# RK3566_VO_Interface.net
KiCad netlist of a schematic drawn in Altium Designer
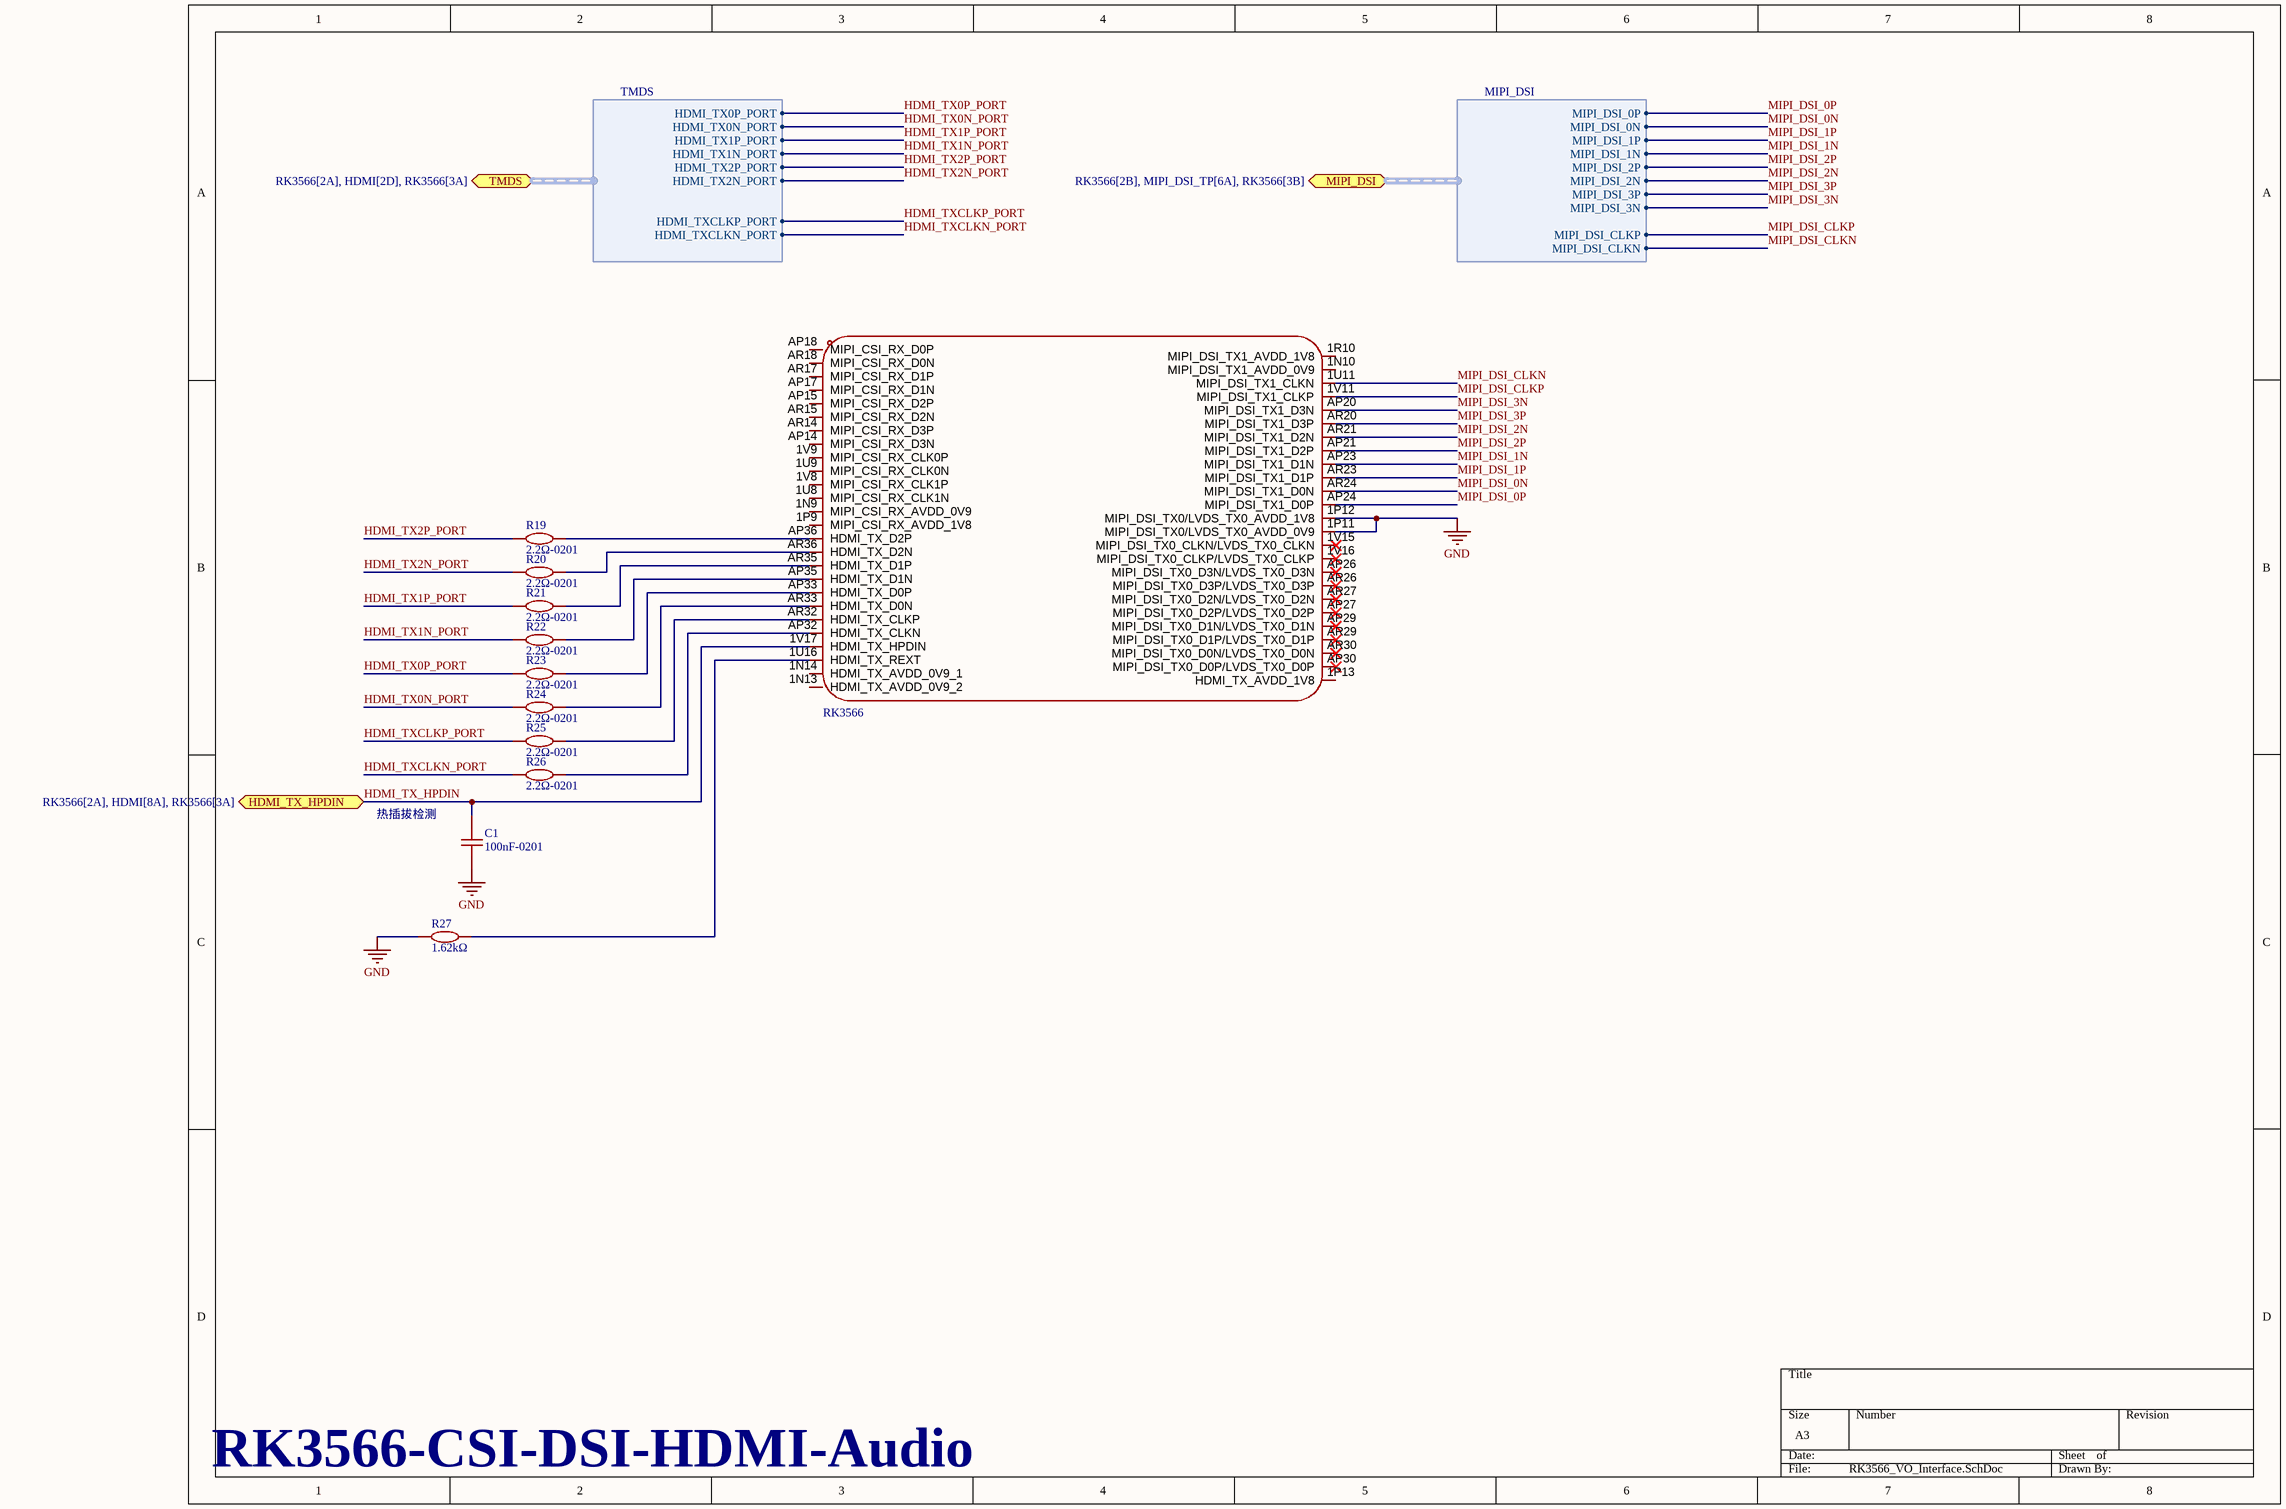
[diagram p0: RK3566_VO_Interface.SchDoc]

(export (version "E")
  (design (tool "Eeschema 10.0.6"))
  (components
    (comp (ref "C1")
      (value "100nF-0201")
      (footprint "C0402")
      (description "CL03A104KO3NNNC")
      (libsource (lib "RLC") (part "100nF-0201"))
    )
    (comp (ref "R19")
      (value "2.2Ω-0201")
      (footprint "R0201")
      (description "小尺寸、重量轻。降低组装成本,与贴片机匹配。适用于波峰焊和回流焊")
      (libsource (lib "RLC") (part "2.2Ω-0201"))
    )
    (comp (ref "R20")
      (value "2.2Ω-0201")
      (footprint "R0201")
      (description "小尺寸、重量轻。降低组装成本,与贴片机匹配。适用于波峰焊和回流焊")
      (libsource (lib "RLC") (part "2.2Ω-0201"))
    )
    (comp (ref "R21")
      (value "2.2Ω-0201")
      (footprint "R0201")
      (description "小尺寸、重量轻。降低组装成本,与贴片机匹配。适用于波峰焊和回流焊")
      (libsource (lib "RLC") (part "2.2Ω-0201"))
    )
    (comp (ref "R22")
      (value "2.2Ω-0201")
      (footprint "R0201")
      (description "小尺寸、重量轻。降低组装成本,与贴片机匹配。适用于波峰焊和回流焊")
      (libsource (lib "RLC") (part "2.2Ω-0201"))
    )
    (comp (ref "R23")
      (value "2.2Ω-0201")
      (footprint "R0201")
      (description "小尺寸、重量轻。降低组装成本,与贴片机匹配。适用于波峰焊和回流焊")
      (libsource (lib "RLC") (part "2.2Ω-0201"))
    )
    (comp (ref "R24")
      (value "2.2Ω-0201")
      (footprint "R0201")
      (description "小尺寸、重量轻。降低组装成本,与贴片机匹配。适用于波峰焊和回流焊")
      (libsource (lib "RLC") (part "2.2Ω-0201"))
    )
    (comp (ref "R25")
      (value "2.2Ω-0201")
      (footprint "R0201")
      (description "小尺寸、重量轻。降低组装成本,与贴片机匹配。适用于波峰焊和回流焊")
      (libsource (lib "RLC") (part "2.2Ω-0201"))
    )
    (comp (ref "R26")
      (value "2.2Ω-0201")
      (footprint "R0201")
      (description "小尺寸、重量轻。降低组装成本,与贴片机匹配。适用于波峰焊和回流焊")
      (libsource (lib "RLC") (part "2.2Ω-0201"))
    )
    (comp (ref "R27")
      (value "1.62kΩ")
      (footprint "R0402")
      (description "特性：无卤环氧树脂。符合RoHS标准。无铅端接产品符合RoHS要求。RoHS豁免电极、电阻元件和玻璃中含有的铅玻璃。减少对环境有害的废物。高组件和设备可靠性。应用：所有通用应用")
      (libsource (lib "RLC") (part "1.62kΩ"))
    )
    (comp (ref "U1")
      (value "RK3566")
      (footprint "BGA-565_L15.5-W14.4-P0.40_RK3566_1")
      (description "BGA-565(15.5x14.4)")
      (libsource (lib "IC") (part "RK3566"))
    )
  )
  (nets
    (net (code "3") (name "/HDMI_TX0N_PORT") (class "Default")
      (node (ref "R24") (pin "1") (pinfunction "1_1") (pintype "passive"))
    )
    (net (code "4") (name "/HDMI_TX0P_PORT") (class "Default")
      (node (ref "R23") (pin "1") (pinfunction "1_1") (pintype "passive"))
    )
    (net (code "5") (name "/HDMI_TX1N_PORT") (class "Default")
      (node (ref "R22") (pin "1") (pinfunction "1_1") (pintype "passive"))
    )
    (net (code "6") (name "/HDMI_TX1P_PORT") (class "Default")
      (node (ref "R21") (pin "1") (pinfunction "1_1") (pintype "passive"))
    )
    (net (code "7") (name "/HDMI_TX2N_PORT") (class "Default")
      (node (ref "R20") (pin "1") (pinfunction "1_1") (pintype "passive"))
    )
    (net (code "8") (name "/HDMI_TX2P_PORT") (class "Default")
      (node (ref "R19") (pin "1") (pinfunction "1_1") (pintype "passive"))
    )
    (net (code "9") (name "/HDMI_TXCLKN_PORT") (class "Default")
      (node (ref "R26") (pin "1") (pinfunction "1_1") (pintype "passive"))
    )
    (net (code "10") (name "/HDMI_TXCLKP_PORT") (class "Default")
      (node (ref "R25") (pin "1") (pinfunction "1_1") (pintype "passive"))
    )
    (net (code "11") (name "/HDMI_TX_HPDIN") (class "Default")
      (node (ref "C1") (pin "2") (pinfunction "2_2") (pintype "passive"))
      (node (ref "U1") (pin "1V17") (pinfunction "HDMI_TX_HPDIN_1V17") (pintype "passive"))
    )
    (net (code "12") (name "/MIPI_DSI_0N") (class "Default")
      (node (ref "U1") (pin "AR24") (pinfunction "MIPI_DSI_TX1_D0N_AR24") (pintype "passive"))
    )
    (net (code "13") (name "/MIPI_DSI_0P") (class "Default")
      (node (ref "U1") (pin "AP24") (pinfunction "MIPI_DSI_TX1_D0P_AP24") (pintype "passive"))
    )
    (net (code "14") (name "/MIPI_DSI_1N") (class "Default")
      (node (ref "U1") (pin "AP23") (pinfunction "MIPI_DSI_TX1_D1N_AP23") (pintype "passive"))
    )
    (net (code "15") (name "/MIPI_DSI_1P") (class "Default")
      (node (ref "U1") (pin "AR23") (pinfunction "MIPI_DSI_TX1_D1P_AR23") (pintype "passive"))
    )
    (net (code "16") (name "/MIPI_DSI_2N") (class "Default")
      (node (ref "U1") (pin "AR21") (pinfunction "MIPI_DSI_TX1_D2N_AR21") (pintype "passive"))
    )
    (net (code "17") (name "/MIPI_DSI_2P") (class "Default")
      (node (ref "U1") (pin "AP21") (pinfunction "MIPI_DSI_TX1_D2P_AP21") (pintype "passive"))
    )
    (net (code "18") (name "/MIPI_DSI_3N") (class "Default")
      (node (ref "U1") (pin "AP20") (pinfunction "MIPI_DSI_TX1_D3N_AP20") (pintype "passive"))
    )
    (net (code "19") (name "/MIPI_DSI_3P") (class "Default")
      (node (ref "U1") (pin "AR20") (pinfunction "MIPI_DSI_TX1_D3P_AR20") (pintype "passive"))
    )
    (net (code "20") (name "/MIPI_DSI_CLKN") (class "Default")
      (node (ref "U1") (pin "1U11") (pinfunction "MIPI_DSI_TX1_CLKN_1U11") (pintype "passive"))
    )
    (net (code "21") (name "/MIPI_DSI_CLKP") (class "Default")
      (node (ref "U1") (pin "1V11") (pinfunction "MIPI_DSI_TX1_CLKP_1V11") (pintype "passive"))
    )
    (net (code "24") (name "GND") (class "Default")
      (node (ref "C1") (pin "1") (pinfunction "1_1") (pintype "passive"))
      (node (ref "R27") (pin "1") (pinfunction "1_1") (pintype "passive"))
      (node (ref "U1") (pin "1P11") (pinfunction "MIPI_DSI_TX0/LVDS_TX0_AVDD_0V9_1P11") (pintype "passive"))
      (node (ref "U1") (pin "1P12") (pinfunction "MIPI_DSI_TX0/LVDS_TX0_AVDD_1V8_1P12") (pintype "passive"))
    )
    (net (code "25") (name "Net-(U1G-HDMI_TX_CLKN)") (class "Default")
      (node (ref "R26") (pin "2") (pinfunction "2_2") (pintype "passive"))
      (node (ref "U1") (pin "AP32") (pinfunction "HDMI_TX_CLKN_AP32") (pintype "passive"))
    )
    (net (code "26") (name "Net-(U1G-HDMI_TX_CLKP)") (class "Default")
      (node (ref "R25") (pin "2") (pinfunction "2_2") (pintype "passive"))
      (node (ref "U1") (pin "AR32") (pinfunction "HDMI_TX_CLKP_AR32") (pintype "passive"))
    )
    (net (code "27") (name "Net-(U1G-HDMI_TX_D0N)") (class "Default")
      (node (ref "R24") (pin "2") (pinfunction "2_2") (pintype "passive"))
      (node (ref "U1") (pin "AR33") (pinfunction "HDMI_TX_D0N_AR33") (pintype "passive"))
    )
    (net (code "28") (name "Net-(U1G-HDMI_TX_D0P)") (class "Default")
      (node (ref "R23") (pin "2") (pinfunction "2_2") (pintype "passive"))
      (node (ref "U1") (pin "AP33") (pinfunction "HDMI_TX_D0P_AP33") (pintype "passive"))
    )
    (net (code "29") (name "Net-(U1G-HDMI_TX_D1N)") (class "Default")
      (node (ref "R22") (pin "2") (pinfunction "2_2") (pintype "passive"))
      (node (ref "U1") (pin "AP35") (pinfunction "HDMI_TX_D1N_AP35") (pintype "passive"))
    )
    (net (code "30") (name "Net-(U1G-HDMI_TX_D1P)") (class "Default")
      (node (ref "R21") (pin "2") (pinfunction "2_2") (pintype "passive"))
      (node (ref "U1") (pin "AR35") (pinfunction "HDMI_TX_D1P_AR35") (pintype "passive"))
    )
    (net (code "31") (name "Net-(U1G-HDMI_TX_D2N)") (class "Default")
      (node (ref "R20") (pin "2") (pinfunction "2_2") (pintype "passive"))
      (node (ref "U1") (pin "AR36") (pinfunction "HDMI_TX_D2N_AR36") (pintype "passive"))
    )
    (net (code "32") (name "Net-(U1G-HDMI_TX_D2P)") (class "Default")
      (node (ref "R19") (pin "2") (pinfunction "2_2") (pintype "passive"))
      (node (ref "U1") (pin "AP36") (pinfunction "HDMI_TX_D2P_AP36") (pintype "passive"))
    )
    (net (code "33") (name "Net-(U1G-HDMI_TX_REXT)") (class "Default")
      (node (ref "R27") (pin "2") (pinfunction "2_2") (pintype "passive"))
      (node (ref "U1") (pin "1U16") (pinfunction "HDMI_TX_REXT_1U16") (pintype "passive"))
    )
    (net (code "34") (name "unconnected-(U1G-HDMI_TX_AVDD_0V9_1-Pad1N14)") (class "Default")
      (node (ref "U1") (pin "1N14") (pinfunction "HDMI_TX_AVDD_0V9_1_1N14") (pintype "passive"))
    )
    (net (code "35") (name "unconnected-(U1G-HDMI_TX_AVDD_0V9_2-Pad1N13)") (class "Default")
      (node (ref "U1") (pin "1N13") (pinfunction "HDMI_TX_AVDD_0V9_2_1N13") (pintype "passive"))
    )
    (net (code "36") (name "unconnected-(U1G-HDMI_TX_AVDD_1V8-Pad1P13)") (class "Default")
      (node (ref "U1") (pin "1P13") (pinfunction "HDMI_TX_AVDD_1V8_1P13") (pintype "passive"))
    )
    (net (code "37") (name "unconnected-(U1G-MIPI_CSI_RX_AVDD_0V9-Pad1N9)") (class "Default")
      (node (ref "U1") (pin "1N9") (pinfunction "MIPI_CSI_RX_AVDD_0V9_1N9") (pintype "passive"))
    )
    (net (code "38") (name "unconnected-(U1G-MIPI_CSI_RX_AVDD_1V8-Pad1P9)") (class "Default")
      (node (ref "U1") (pin "1P9") (pinfunction "MIPI_CSI_RX_AVDD_1V8_1P9") (pintype "passive"))
    )
    (net (code "39") (name "unconnected-(U1G-MIPI_CSI_RX_CLK0N-Pad1U9)") (class "Default")
      (node (ref "U1") (pin "1U9") (pinfunction "MIPI_CSI_RX_CLK0N_1U9") (pintype "passive"))
    )
    (net (code "40") (name "unconnected-(U1G-MIPI_CSI_RX_CLK0P-Pad1V9)") (class "Default")
      (node (ref "U1") (pin "1V9") (pinfunction "MIPI_CSI_RX_CLK0P_1V9") (pintype "passive"))
    )
    (net (code "41") (name "unconnected-(U1G-MIPI_CSI_RX_CLK1N-Pad1U8)") (class "Default")
      (node (ref "U1") (pin "1U8") (pinfunction "MIPI_CSI_RX_CLK1N_1U8") (pintype "passive"))
    )
    (net (code "42") (name "unconnected-(U1G-MIPI_CSI_RX_CLK1P-Pad1V8)") (class "Default")
      (node (ref "U1") (pin "1V8") (pinfunction "MIPI_CSI_RX_CLK1P_1V8") (pintype "passive"))
    )
    (net (code "43") (name "unconnected-(U1G-MIPI_CSI_RX_D0N-PadAR18)") (class "Default")
      (node (ref "U1") (pin "AR18") (pinfunction "MIPI_CSI_RX_D0N_AR18") (pintype "passive"))
    )
    (net (code "44") (name "unconnected-(U1G-MIPI_CSI_RX_D0P-PadAP18)") (class "Default")
      (node (ref "U1") (pin "AP18") (pinfunction "MIPI_CSI_RX_D0P_AP18") (pintype "passive"))
    )
    (net (code "45") (name "unconnected-(U1G-MIPI_CSI_RX_D1N-PadAP17)") (class "Default")
      (node (ref "U1") (pin "AP17") (pinfunction "MIPI_CSI_RX_D1N_AP17") (pintype "passive"))
    )
    (net (code "46") (name "unconnected-(U1G-MIPI_CSI_RX_D1P-PadAR17)") (class "Default")
      (node (ref "U1") (pin "AR17") (pinfunction "MIPI_CSI_RX_D1P_AR17") (pintype "passive"))
    )
    (net (code "47") (name "unconnected-(U1G-MIPI_CSI_RX_D2N-PadAR15)") (class "Default")
      (node (ref "U1") (pin "AR15") (pinfunction "MIPI_CSI_RX_D2N_AR15") (pintype "passive"))
    )
    (net (code "48") (name "unconnected-(U1G-MIPI_CSI_RX_D2P-PadAP15)") (class "Default")
      (node (ref "U1") (pin "AP15") (pinfunction "MIPI_CSI_RX_D2P_AP15") (pintype "passive"))
    )
    (net (code "49") (name "unconnected-(U1G-MIPI_CSI_RX_D3N-PadAP14)") (class "Default")
      (node (ref "U1") (pin "AP14") (pinfunction "MIPI_CSI_RX_D3N_AP14") (pintype "passive"))
    )
    (net (code "50") (name "unconnected-(U1G-MIPI_CSI_RX_D3P-PadAR14)") (class "Default")
      (node (ref "U1") (pin "AR14") (pinfunction "MIPI_CSI_RX_D3P_AR14") (pintype "passive"))
    )
    (net (code "51") (name "unconnected-(U1G-MIPI_DSI_TX0_CLKN{slash}LVDS_TX0_CLKN-Pad1V15)") (class "Default")
      (node (ref "U1") (pin "1V15") (pinfunction "MIPI_DSI_TX0_CLKN/LVDS_TX0_CLKN_1V15") (pintype "passive+no_connect"))
    )
    (net (code "52") (name "unconnected-(U1G-MIPI_DSI_TX0_CLKP{slash}LVDS_TX0_CLKP-Pad1V16)") (class "Default")
      (node (ref "U1") (pin "1V16") (pinfunction "MIPI_DSI_TX0_CLKP/LVDS_TX0_CLKP_1V16") (pintype "passive+no_connect"))
    )
    (net (code "53") (name "unconnected-(U1G-MIPI_DSI_TX0_D0N{slash}LVDS_TX0_D0N-PadAR30)") (class "Default")
      (node (ref "U1") (pin "AR30") (pinfunction "MIPI_DSI_TX0_D0N/LVDS_TX0_D0N_AR30") (pintype "passive+no_connect"))
    )
    (net (code "54") (name "unconnected-(U1G-MIPI_DSI_TX0_D0P{slash}LVDS_TX0_D0P-PadAP30)") (class "Default")
      (node (ref "U1") (pin "AP30") (pinfunction "MIPI_DSI_TX0_D0P/LVDS_TX0_D0P_AP30") (pintype "passive+no_connect"))
    )
    (net (code "55") (name "unconnected-(U1G-MIPI_DSI_TX0_D1N{slash}LVDS_TX0_D1N-PadAP29)") (class "Default")
      (node (ref "U1") (pin "AP29") (pinfunction "MIPI_DSI_TX0_D1N/LVDS_TX0_D1N_AP29") (pintype "passive+no_connect"))
    )
    (net (code "56") (name "unconnected-(U1G-MIPI_DSI_TX0_D1P{slash}LVDS_TX0_D1P-PadAR29)") (class "Default")
      (node (ref "U1") (pin "AR29") (pinfunction "MIPI_DSI_TX0_D1P/LVDS_TX0_D1P_AR29") (pintype "passive+no_connect"))
    )
    (net (code "57") (name "unconnected-(U1G-MIPI_DSI_TX0_D2N{slash}LVDS_TX0_D2N-PadAR27)") (class "Default")
      (node (ref "U1") (pin "AR27") (pinfunction "MIPI_DSI_TX0_D2N/LVDS_TX0_D2N_AR27") (pintype "passive+no_connect"))
    )
    (net (code "58") (name "unconnected-(U1G-MIPI_DSI_TX0_D2P{slash}LVDS_TX0_D2P-PadAP27)") (class "Default")
      (node (ref "U1") (pin "AP27") (pinfunction "MIPI_DSI_TX0_D2P/LVDS_TX0_D2P_AP27") (pintype "passive+no_connect"))
    )
    (net (code "59") (name "unconnected-(U1G-MIPI_DSI_TX0_D3N{slash}LVDS_TX0_D3N-PadAP26)") (class "Default")
      (node (ref "U1") (pin "AP26") (pinfunction "MIPI_DSI_TX0_D3N/LVDS_TX0_D3N_AP26") (pintype "passive+no_connect"))
    )
    (net (code "60") (name "unconnected-(U1G-MIPI_DSI_TX0_D3P{slash}LVDS_TX0_D3P-PadAR26)") (class "Default")
      (node (ref "U1") (pin "AR26") (pinfunction "MIPI_DSI_TX0_D3P/LVDS_TX0_D3P_AR26") (pintype "passive+no_connect"))
    )
    (net (code "61") (name "unconnected-(U1G-MIPI_DSI_TX1_AVDD_0V9-Pad1N10)") (class "Default")
      (node (ref "U1") (pin "1N10") (pinfunction "MIPI_DSI_TX1_AVDD_0V9_1N10") (pintype "passive"))
    )
    (net (code "62") (name "unconnected-(U1G-MIPI_DSI_TX1_AVDD_1V8-Pad1R10)") (class "Default")
      (node (ref "U1") (pin "1R10") (pinfunction "MIPI_DSI_TX1_AVDD_1V8_1R10") (pintype "passive"))
    )
  )
)
